# STorM32_NT_imu_v10-mpu9250.net
KiCad netlist of a schematic drawn in EAGLE
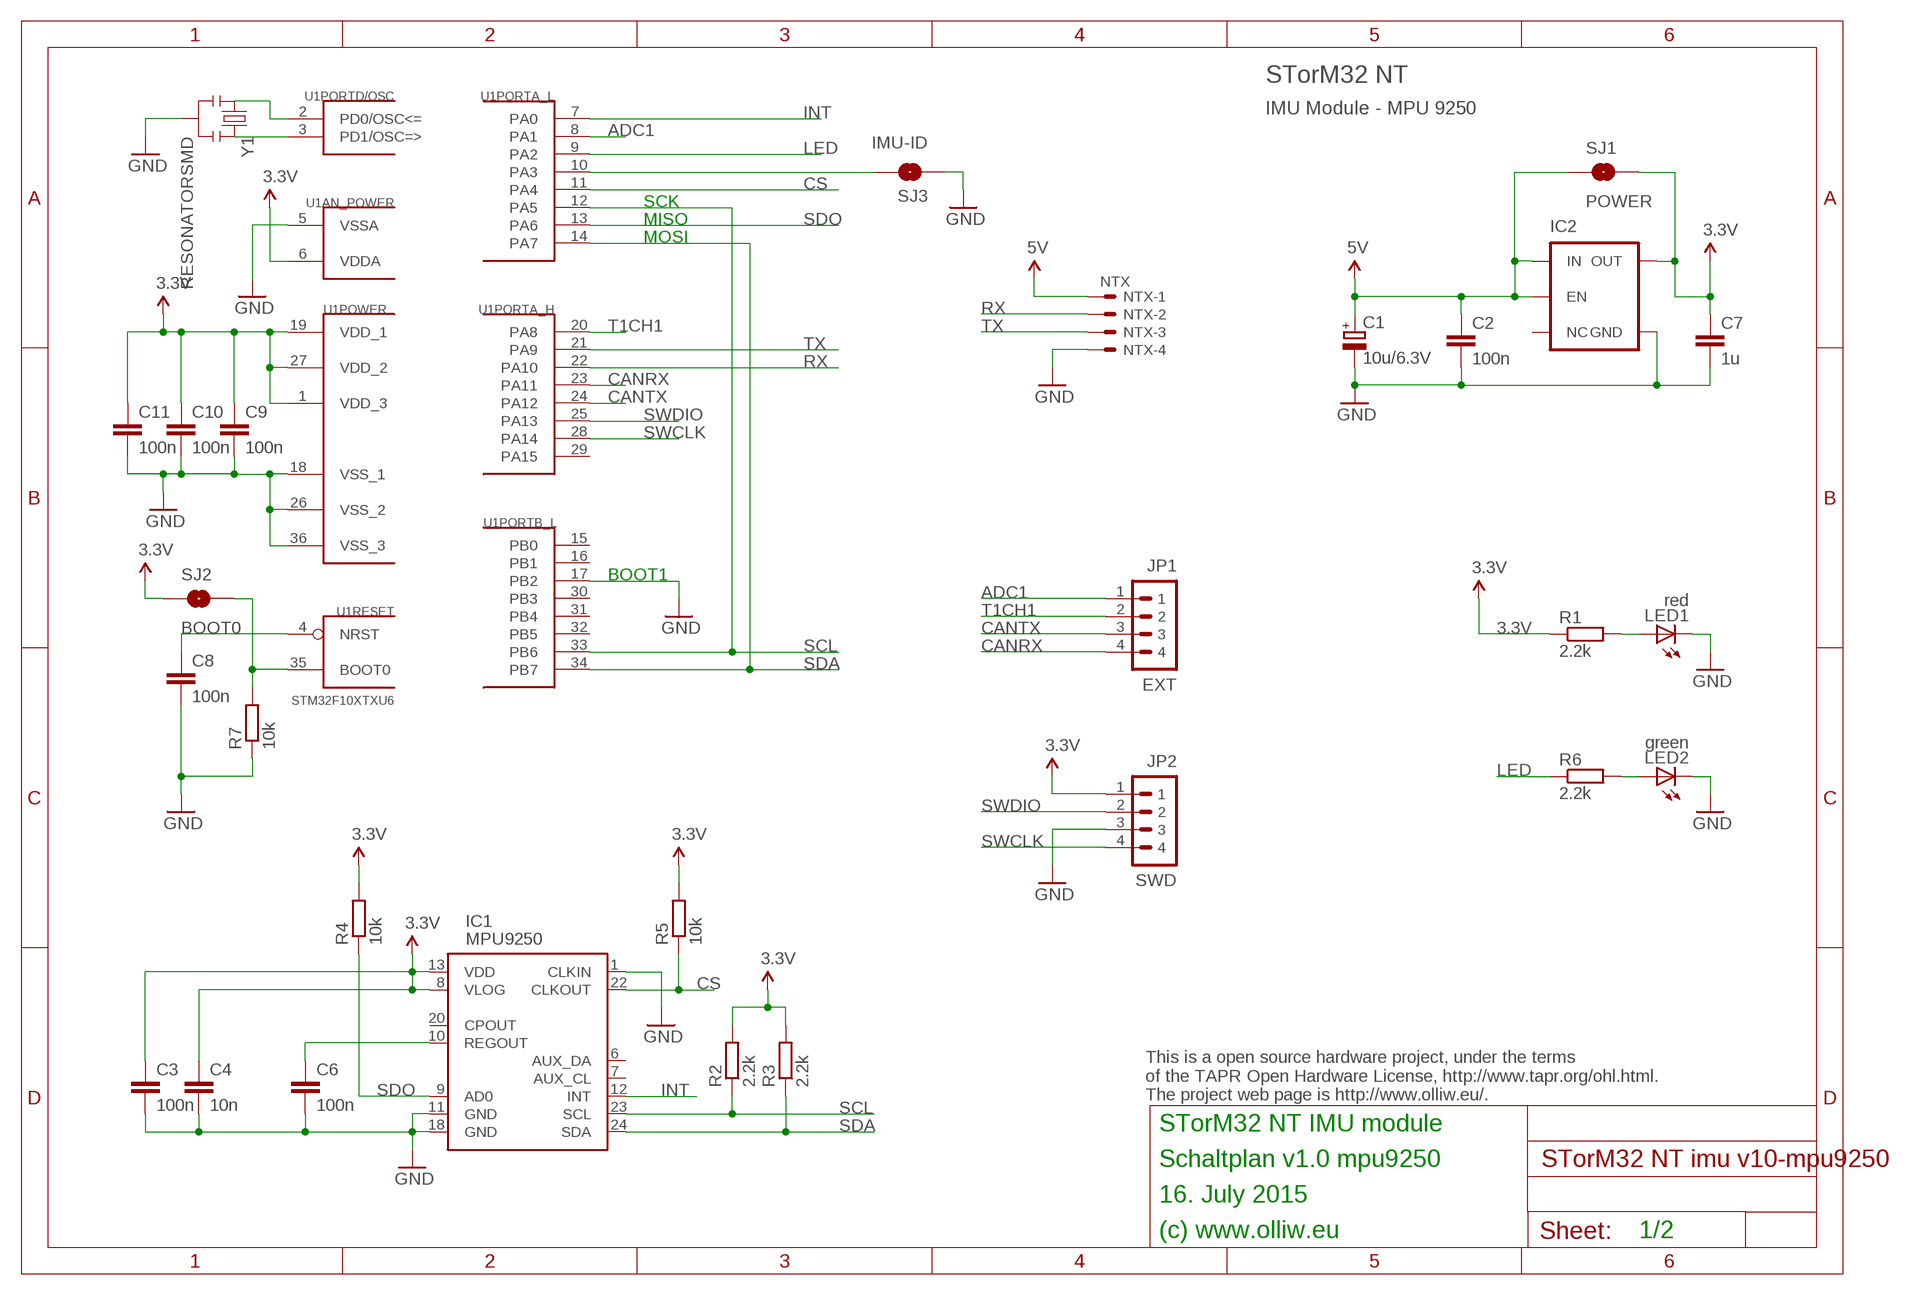
[diagram p0: schematic, sheet 1]

(export (version "E")
  (design (tool "Eeschema 10.0.6"))
  (components
    (comp (ref "C1")
      (value "10u/6.3V")
      (footprint "eagle-import:SMC_B")
      (libsource (lib "eagle-import") (part "CPOL-EUSMCB"))
    )
    (comp (ref "C2")
      (value "100n")
      (footprint "eagle-import:C0603")
      (libsource (lib "eagle-import") (part "C-EUC0603"))
    )
    (comp (ref "C3")
      (value "100n")
      (footprint "eagle-import:C0603")
      (libsource (lib "eagle-import") (part "C-EUC0603"))
    )
    (comp (ref "C4")
      (value "10n")
      (footprint "eagle-import:C0603")
      (libsource (lib "eagle-import") (part "C-EUC0603"))
    )
    (comp (ref "C6")
      (value "100n")
      (footprint "eagle-import:C0603")
      (libsource (lib "eagle-import") (part "C-EUC0603"))
    )
    (comp (ref "C7")
      (value "1u")
      (footprint "eagle-import:C0603")
      (libsource (lib "eagle-import") (part "C-EUC0603"))
    )
    (comp (ref "C8")
      (value "100n")
      (footprint "eagle-import:C0402")
      (libsource (lib "eagle-import") (part "C-EUC0402"))
    )
    (comp (ref "C9")
      (value "100n")
      (footprint "eagle-import:C0603")
      (libsource (lib "eagle-import") (part "C-EUC0603"))
    )
    (comp (ref "C10")
      (value "100n")
      (footprint "eagle-import:C0402")
      (libsource (lib "eagle-import") (part "C-EUC0402"))
    )
    (comp (ref "C11")
      (value "100n")
      (footprint "eagle-import:C0603")
      (libsource (lib "eagle-import") (part "C-EUC0603"))
    )
    (comp (ref "IC1")
      (value "MPU9250")
      (footprint "eagle-import:QFN-24-3X3")
      (libsource (lib "eagle-import") (part "IMU3000QFN-24-0.4MIL"))
    )
    (comp (ref "IC2")
      (value "V_REG_TPS76433SOT23-5")
      (footprint "eagle-import:SOT23-5")
      (libsource (lib "eagle-import") (part "V_REG_TPS76433SOT23-5"))
    )
    (comp (ref "JP1")
      (value "EXT")
      (footprint "eagle-import:4X1_1P27_OCT_BILEX")
      (libsource (lib "eagle-import") (part "P4X1_1P27-OCT_BILEX"))
    )
    (comp (ref "JP2")
      (value "SWD")
      (footprint "eagle-import:4X1_1P27_OCT_BILEX")
      (libsource (lib "eagle-import") (part "P4X1_1P27-OCT_BILEX"))
    )
    (comp (ref "LED1")
      (value "red")
      (footprint "eagle-import:CHIPLED_0603")
      (libsource (lib "eagle-import") (part "LEDCHIPLED_0603"))
    )
    (comp (ref "LED2")
      (value "green")
      (footprint "eagle-import:CHIPLED_0603")
      (libsource (lib "eagle-import") (part "LEDCHIPLED_0603"))
    )
    (comp (ref "NTX")
      (value "NTX")
      (footprint "eagle-import:SM04B-SRSS-TB")
      (libsource (lib "eagle-import") (part "?M04B-SRSS-TBS"))
    )
    (comp (ref "R1")
      (value "2.2k")
      (footprint "eagle-import:R0603")
      (libsource (lib "eagle-import") (part "R-EU_R0603"))
    )
    (comp (ref "R2")
      (value "2.2k")
      (footprint "eagle-import:R0603")
      (libsource (lib "eagle-import") (part "R-EU_R0603"))
    )
    (comp (ref "R3")
      (value "2.2k")
      (footprint "eagle-import:R0603")
      (libsource (lib "eagle-import") (part "R-EU_R0603"))
    )
    (comp (ref "R4")
      (value "10k")
      (footprint "eagle-import:R0603")
      (libsource (lib "eagle-import") (part "R-EU_R0603"))
    )
    (comp (ref "R5")
      (value "10k")
      (footprint "eagle-import:R0603")
      (libsource (lib "eagle-import") (part "R-EU_R0603"))
    )
    (comp (ref "R6")
      (value "2.2k")
      (footprint "eagle-import:R0603")
      (libsource (lib "eagle-import") (part "R-EU_R0603"))
    )
    (comp (ref "R7")
      (value "10k")
      (footprint "eagle-import:R0603")
      (libsource (lib "eagle-import") (part "R-EU_R0603"))
    )
    (comp (ref "SJ1")
      (value "POWER")
      (footprint "eagle-import:SJ_2S-NO")
      (libsource (lib "eagle-import") (part "SOLDERJUMPERNO"))
    )
    (comp (ref "SJ2")
      (value "BOOT0")
      (footprint "eagle-import:SJ_2S-NO")
      (libsource (lib "eagle-import") (part "SOLDERJUMPERNO"))
    )
    (comp (ref "SJ3")
      (value "IMU-ID")
      (footprint "eagle-import:SJ_2S-NO")
      (libsource (lib "eagle-import") (part "SOLDERJUMPERNO"))
    )
    (comp (ref "U1")
      (value "STM32F10XTXU6")
      (footprint "eagle-import:VFQFPN36")
      (libsource (lib "eagle-import") (part "STM32F10XTXU6"))
    )
    (comp (ref "Y1")
      (value "RESONATORSMD")
      (footprint "eagle-import:RESONATOR-SMD")
      (libsource (lib "eagle-import") (part "RESONATORSMD"))
    )
  )
  (nets
    (net (code "1") (name "/ADC1") (class "Default")
      (node (ref "JP1") (pin "1") (pinfunction "1_1") (pintype "passive"))
      (node (ref "U1") (pin "8") (pinfunction "PA1_8") (pintype "bidirectional"))
    )
    (net (code "2") (name "/CANRX") (class "Default")
      (node (ref "JP1") (pin "4") (pinfunction "4_4") (pintype "passive"))
      (node (ref "U1") (pin "23") (pinfunction "PA11_23") (pintype "bidirectional"))
    )
    (net (code "3") (name "/CANTX") (class "Default")
      (node (ref "JP1") (pin "3") (pinfunction "3_3") (pintype "passive"))
      (node (ref "U1") (pin "24") (pinfunction "PA12_24") (pintype "bidirectional"))
    )
    (net (code "4") (name "/CS") (class "Default")
      (node (ref "IC1") (pin "22") (pinfunction "CLKOUT_22") (pintype "bidirectional"))
      (node (ref "R5") (pin "1") (pinfunction "1_1") (pintype "passive"))
      (node (ref "U1") (pin "11") (pinfunction "PA4_11") (pintype "bidirectional"))
    )
    (net (code "5") (name "/INT") (class "Default")
      (node (ref "IC1") (pin "12") (pinfunction "INT_12") (pintype "bidirectional"))
      (node (ref "U1") (pin "7") (pinfunction "PA0_7") (pintype "bidirectional"))
    )
    (net (code "6") (name "/LED") (class "Default")
      (node (ref "R6") (pin "1") (pinfunction "1_1") (pintype "passive"))
      (node (ref "U1") (pin "9") (pinfunction "PA2_9") (pintype "bidirectional"))
    )
    (net (code "7") (name "/RX") (class "Default")
      (node (ref "NTX") (pin "2") (pinfunction "S_2") (pintype "passive"))
      (node (ref "U1") (pin "22") (pinfunction "PA10_22") (pintype "bidirectional"))
    )
    (net (code "8") (name "/SCL") (class "Default")
      (node (ref "IC1") (pin "23") (pinfunction "SCL_23") (pintype "bidirectional"))
      (node (ref "R2") (pin "1") (pinfunction "1_1") (pintype "passive"))
      (node (ref "U1") (pin "12") (pinfunction "PA5_12") (pintype "bidirectional"))
      (node (ref "U1") (pin "33") (pinfunction "PB6_33") (pintype "bidirectional"))
    )
    (net (code "9") (name "/SDA") (class "Default")
      (node (ref "IC1") (pin "24") (pinfunction "SDA_24") (pintype "bidirectional"))
      (node (ref "R3") (pin "1") (pinfunction "1_1") (pintype "passive"))
      (node (ref "U1") (pin "14") (pinfunction "PA7_14") (pintype "bidirectional"))
      (node (ref "U1") (pin "34") (pinfunction "PB7_34") (pintype "bidirectional"))
    )
    (net (code "10") (name "/SDO") (class "Default")
      (node (ref "IC1") (pin "9") (pinfunction "AD0_9") (pintype "bidirectional"))
      (node (ref "R4") (pin "1") (pinfunction "1_1") (pintype "passive"))
      (node (ref "U1") (pin "13") (pinfunction "PA6_13") (pintype "bidirectional"))
    )
    (net (code "11") (name "/SWCLK") (class "Default")
      (node (ref "JP2") (pin "4") (pinfunction "4_4") (pintype "passive"))
      (node (ref "U1") (pin "28") (pinfunction "PA14_28") (pintype "bidirectional"))
    )
    (net (code "12") (name "/SWDIO") (class "Default")
      (node (ref "JP2") (pin "2") (pinfunction "2_2") (pintype "passive"))
      (node (ref "U1") (pin "25") (pinfunction "PA13_25") (pintype "bidirectional"))
    )
    (net (code "13") (name "/T1CH1") (class "Default")
      (node (ref "JP1") (pin "2") (pinfunction "2_2") (pintype "passive"))
      (node (ref "U1") (pin "20") (pinfunction "PA8_20") (pintype "bidirectional"))
    )
    (net (code "14") (name "/TX") (class "Default")
      (node (ref "NTX") (pin "3") (pinfunction "S_3") (pintype "passive"))
      (node (ref "U1") (pin "21") (pinfunction "PA9_21") (pintype "bidirectional"))
    )
    (net (code "15") (name "3.3V") (class "Default")
      (node (ref "C10") (pin "1") (pinfunction "1_1") (pintype "passive"))
      (node (ref "C11") (pin "1") (pinfunction "1_1") (pintype "passive"))
      (node (ref "C3") (pin "1") (pinfunction "1_1") (pintype "passive"))
      (node (ref "C4") (pin "1") (pinfunction "1_1") (pintype "passive"))
      (node (ref "C7") (pin "1") (pinfunction "1_1") (pintype "passive"))
      (node (ref "C9") (pin "1") (pinfunction "1_1") (pintype "passive"))
      (node (ref "IC1") (pin "13") (pinfunction "VDD_13") (pintype "bidirectional"))
      (node (ref "IC1") (pin "8") (pinfunction "VLOG_8") (pintype "bidirectional"))
      (node (ref "IC2") (pin "5") (pinfunction "OUT_5") (pintype "passive"))
      (node (ref "JP2") (pin "1") (pinfunction "1_1") (pintype "passive"))
      (node (ref "R1") (pin "1") (pinfunction "1_1") (pintype "passive"))
      (node (ref "R2") (pin "2") (pinfunction "2_2") (pintype "passive"))
      (node (ref "R3") (pin "2") (pinfunction "2_2") (pintype "passive"))
      (node (ref "R4") (pin "2") (pinfunction "2_2") (pintype "passive"))
      (node (ref "R5") (pin "2") (pinfunction "2_2") (pintype "passive"))
      (node (ref "SJ1") (pin "2") (pinfunction "2_2") (pintype "passive"))
      (node (ref "SJ2") (pin "1") (pinfunction "1_1") (pintype "passive"))
      (node (ref "U1") (pin "1") (pinfunction "VDD_3_1") (pintype "power_in"))
      (node (ref "U1") (pin "19") (pinfunction "VDD_1_19") (pintype "power_in"))
      (node (ref "U1") (pin "27") (pinfunction "VDD_2_27") (pintype "power_in"))
      (node (ref "U1") (pin "6") (pinfunction "VDDA_6") (pintype "power_in"))
    )
    (net (code "16") (name "5V") (class "Default")
      (node (ref "C1") (pin "+") (pinfunction "+_+") (pintype "passive"))
      (node (ref "C2") (pin "1") (pinfunction "1_1") (pintype "passive"))
      (node (ref "IC2") (pin "1") (pinfunction "IN_1") (pintype "input"))
      (node (ref "IC2") (pin "3") (pinfunction "EN_3") (pintype "input"))
      (node (ref "NTX") (pin "1") (pinfunction "S_1") (pintype "passive"))
      (node (ref "SJ1") (pin "1") (pinfunction "1_1") (pintype "passive"))
    )
    (net (code "17") (name "GND") (class "Default")
      (node (ref "C1") (pin "-") (pinfunction "-_-") (pintype "passive"))
      (node (ref "C10") (pin "2") (pinfunction "2_2") (pintype "passive"))
      (node (ref "C11") (pin "2") (pinfunction "2_2") (pintype "passive"))
      (node (ref "C2") (pin "2") (pinfunction "2_2") (pintype "passive"))
      (node (ref "C3") (pin "2") (pinfunction "2_2") (pintype "passive"))
      (node (ref "C4") (pin "2") (pinfunction "2_2") (pintype "passive"))
      (node (ref "C6") (pin "2") (pinfunction "2_2") (pintype "passive"))
      (node (ref "C7") (pin "2") (pinfunction "2_2") (pintype "passive"))
      (node (ref "C8") (pin "2") (pinfunction "2_2") (pintype "passive"))
      (node (ref "C9") (pin "2") (pinfunction "2_2") (pintype "passive"))
      (node (ref "IC1") (pin "1") (pinfunction "CLKIN_1") (pintype "bidirectional"))
      (node (ref "IC1") (pin "11") (pinfunction "GND_11") (pintype "bidirectional"))
      (node (ref "IC1") (pin "18") (pinfunction "GND_18") (pintype "bidirectional"))
      (node (ref "IC2") (pin "2") (pinfunction "GND_2") (pintype "input"))
      (node (ref "JP2") (pin "3") (pinfunction "3_3") (pintype "passive"))
      (node (ref "LED1") (pin "C") (pinfunction "C_C") (pintype "passive"))
      (node (ref "LED2") (pin "C") (pinfunction "C_C") (pintype "passive"))
      (node (ref "NTX") (pin "4") (pinfunction "S_4") (pintype "passive"))
      (node (ref "R7") (pin "1") (pinfunction "1_1") (pintype "passive"))
      (node (ref "SJ3") (pin "1") (pinfunction "1_1") (pintype "passive"))
      (node (ref "U1") (pin "17") (pinfunction "PB2_17") (pintype "bidirectional"))
      (node (ref "U1") (pin "18") (pinfunction "VSS_1_18") (pintype "power_in"))
      (node (ref "U1") (pin "26") (pinfunction "VSS_2_26") (pintype "power_in"))
      (node (ref "U1") (pin "36") (pinfunction "VSS_3_36") (pintype "power_in"))
      (node (ref "U1") (pin "5") (pinfunction "VSSA_5") (pintype "power_in"))
      (node (ref "Y1") (pin "2") (pinfunction "2_2") (pintype "passive"))
    )
    (net (code "18") (name "Net-(IC1-REGOUT)") (class "Default")
      (node (ref "C6") (pin "1") (pinfunction "1_1") (pintype "passive"))
      (node (ref "IC1") (pin "10") (pinfunction "REGOUT_10") (pintype "bidirectional"))
    )
    (net (code "19") (name "Net-(LED1-PadA)") (class "Default")
      (node (ref "LED1") (pin "A") (pinfunction "A_A") (pintype "passive"))
      (node (ref "R1") (pin "2") (pinfunction "2_2") (pintype "passive"))
    )
    (net (code "20") (name "Net-(LED2-PadA)") (class "Default")
      (node (ref "LED2") (pin "A") (pinfunction "A_A") (pintype "passive"))
      (node (ref "R6") (pin "2") (pinfunction "2_2") (pintype "passive"))
    )
    (net (code "21") (name "Net-(U1C-PA3)") (class "Default")
      (node (ref "SJ3") (pin "2") (pinfunction "2_2") (pintype "passive"))
      (node (ref "U1") (pin "10") (pinfunction "PA3_10") (pintype "bidirectional"))
    )
    (net (code "22") (name "Net-(U1E-PD0{slash}OSC<=)") (class "Default")
      (node (ref "U1") (pin "2") (pinfunction "PD0/OSC<=_2") (pintype "bidirectional"))
      (node (ref "Y1") (pin "1") (pinfunction "1_1") (pintype "passive"))
    )
    (net (code "23") (name "Net-(U1E-PD1{slash}OSC=>)") (class "Default")
      (node (ref "U1") (pin "3") (pinfunction "PD1/OSC=>_3") (pintype "bidirectional"))
      (node (ref "Y1") (pin "3") (pinfunction "3_3") (pintype "passive"))
    )
    (net (code "24") (name "Net-(U1G-BOOT0)") (class "Default")
      (node (ref "R7") (pin "2") (pinfunction "2_2") (pintype "passive"))
      (node (ref "SJ2") (pin "2") (pinfunction "2_2") (pintype "passive"))
      (node (ref "U1") (pin "35") (pinfunction "BOOT0_35") (pintype "input"))
    )
    (net (code "25") (name "Net-(U1G-NRST)") (class "Default")
      (node (ref "C8") (pin "1") (pinfunction "1_1") (pintype "passive"))
      (node (ref "U1") (pin "4") (pinfunction "NRST_4") (pintype "input"))
    )
    (net (code "26") (name "unconnected-(IC1-AUX_CL-Pad7)") (class "Default")
      (node (ref "IC1") (pin "7") (pinfunction "AUX_CL_7") (pintype "bidirectional"))
    )
    (net (code "27") (name "unconnected-(IC1-AUX_DA-Pad6)") (class "Default")
      (node (ref "IC1") (pin "6") (pinfunction "AUX_DA_6") (pintype "bidirectional"))
    )
    (net (code "28") (name "unconnected-(IC1-CPOUT-Pad20)") (class "Default")
      (node (ref "IC1") (pin "20") (pinfunction "CPOUT_20") (pintype "bidirectional"))
    )
    (net (code "29") (name "unconnected-(IC2-NC-Pad4)") (class "Default")
      (node (ref "IC2") (pin "4") (pinfunction "NC_4") (pintype "input"))
    )
    (net (code "30") (name "unconnected-(U1B-PA15-Pad29)") (class "Default")
      (node (ref "U1") (pin "29") (pinfunction "PA15_29") (pintype "bidirectional"))
    )
    (net (code "31") (name "unconnected-(U1D-PB0-Pad15)") (class "Default")
      (node (ref "U1") (pin "15") (pinfunction "PB0_15") (pintype "bidirectional"))
    )
    (net (code "32") (name "unconnected-(U1D-PB1-Pad16)") (class "Default")
      (node (ref "U1") (pin "16") (pinfunction "PB1_16") (pintype "bidirectional"))
    )
    (net (code "33") (name "unconnected-(U1D-PB3-Pad30)") (class "Default")
      (node (ref "U1") (pin "30") (pinfunction "PB3_30") (pintype "bidirectional"))
    )
    (net (code "34") (name "unconnected-(U1D-PB4-Pad31)") (class "Default")
      (node (ref "U1") (pin "31") (pinfunction "PB4_31") (pintype "bidirectional"))
    )
    (net (code "35") (name "unconnected-(U1D-PB5-Pad32)") (class "Default")
      (node (ref "U1") (pin "32") (pinfunction "PB5_32") (pintype "bidirectional"))
    )
  )
)
